# i2c_pullups.net
KiCad netlist of a schematic drawn in Altium Designer
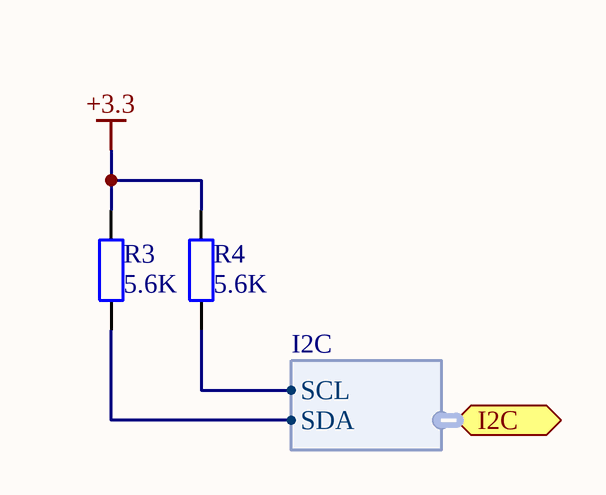
[diagram p0: i2c pullups.SchDoc]

(export (version "E")
  (design (tool "Eeschema 10.0.6"))
  (components
    (comp (ref "R3")
      (value "5.6K")
      (footprint "R0603")
      (description "Resistor")
      (fields (field (name "Comment") "Res2") (field (name "PUBLISHER") "Altium Limited"))
      (libsource (lib "Miscellaneous Devices") (part "Res2"))
    )
    (comp (ref "R4")
      (value "5.6K")
      (footprint "R0603")
      (description "Resistor")
      (fields (field (name "Comment") "Res2") (field (name "PUBLISHER") "Altium Limited"))
      (libsource (lib "Miscellaneous Devices") (part "Res2"))
    )
  )
  (nets
    (net (code "2") (name "+3.3") (class "Default")
      (node (ref "R3") (pin "2") (pinfunction "2_2") (pintype "passive"))
      (node (ref "R4") (pin "2") (pinfunction "2_2") (pintype "passive"))
    )
    (net (code "3") (name "/SCL") (class "Default")
      (node (ref "R4") (pin "1") (pinfunction "1_1") (pintype "passive"))
    )
    (net (code "4") (name "/SDA") (class "Default")
      (node (ref "R3") (pin "1") (pinfunction "1_1") (pintype "passive"))
    )
  )
)
